# 5V_Power_Supply.net
KiCad netlist of a schematic drawn in Altium Designer
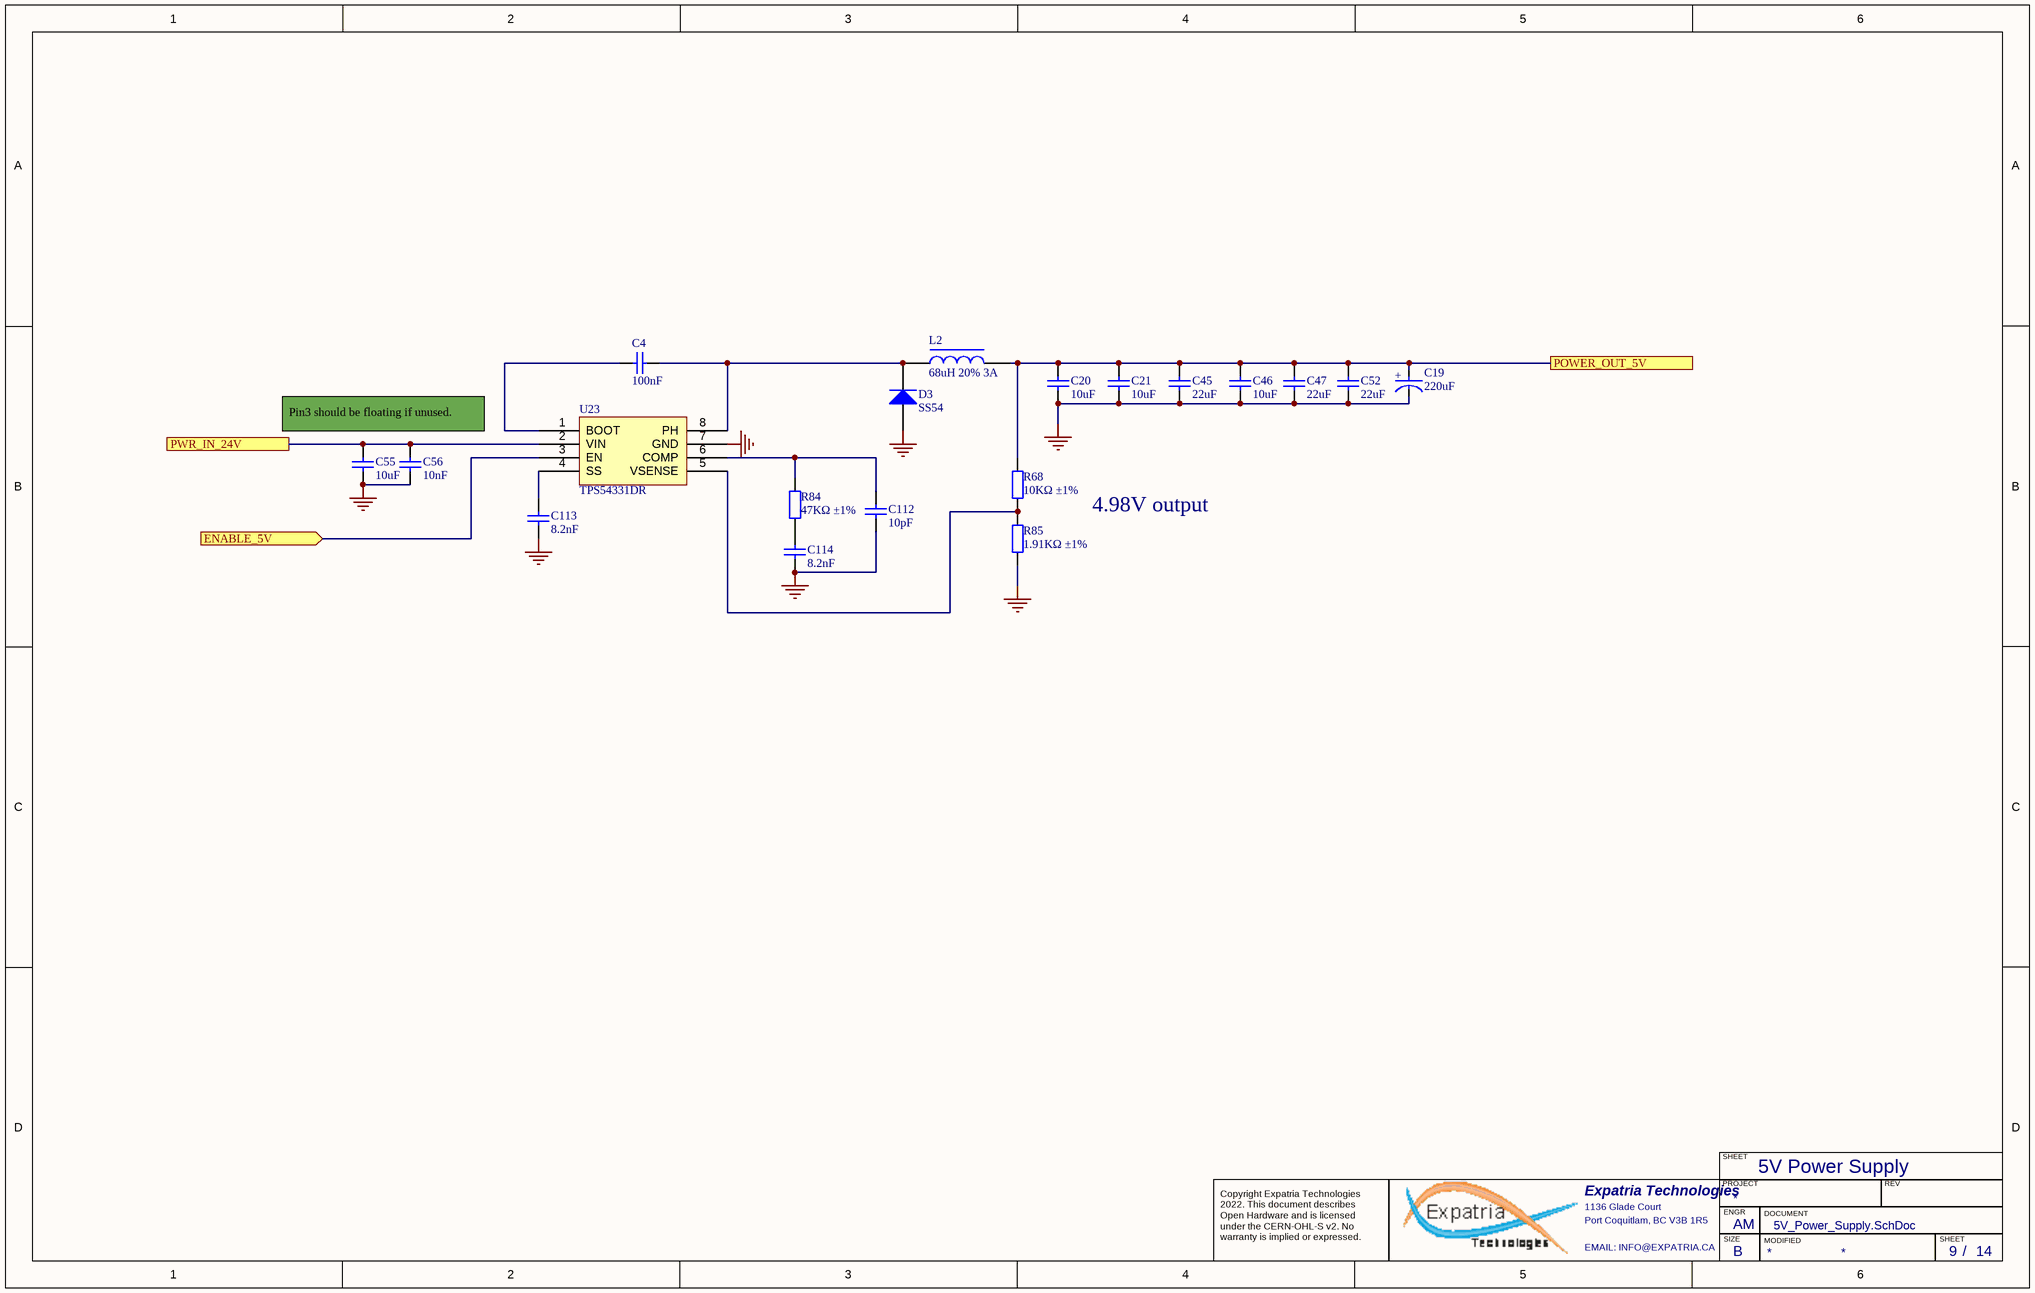
[diagram p0: 5V_Power_Supply.SchDoc]

(export (version "E")
  (design (tool "Eeschema 10.0.6"))
  (components
    (comp (ref "C4")
      (value "100nF")
      (footprint "0603_C")
      (description "50V 100nF X7R ±10% 0603 Multilayer Ceramic Capacitors MLCC - SMD/SMT ROHS")
      (fields
        (field (name "MANUFACTURER") "YAGEO")
        (field (name "MANUFACTURER PART NUMBER") "CC0603KRX7R9BB104")
      )
      (libsource (lib "Sienci_Labs") (part "0603 100nF (104) 10% 50V"))
    )
    (comp (ref "C19")
      (value "UUD1H221MNL1GS")
      (footprint "FP-FKG-MFG")
      (description "CAP ALUM 220UF 20% 50V SMD")
      (fields
        (field (name "TOLERANCE") "20%")
        (field (name "CAPACITANCE") "220uF")
        (field (name "MANUFACTURER") "Nichicon")
        (field (name "SOURCE") "Sienci_Labs.SchLib")
      )
      (libsource (lib "Cambridge Mobile Telematics, Inc") (part "UUD1H221MNL1GS"))
    )
    (comp (ref "C20")
      (value "10uF")
      (footprint "1206_C")
      (description "50V 10uF X5R ±10% 1206 Multilayer Ceramic Capacitors MLCC - SMD/SMT ROHS")
      (fields
        (field (name "MANUFACTURER") "Samsung Electro-Mechanics")
        (field (name "MANUFACTURER PART NUMBER") "CL31A106KBHNNNE")
      )
      (libsource (lib "Sienci_Labs") (part "1206 10uF (106) 10% 50V"))
    )
    (comp (ref "C21")
      (value "10uF")
      (footprint "1206_C")
      (description "50V 10uF X5R ±10% 1206 Multilayer Ceramic Capacitors MLCC - SMD/SMT ROHS")
      (fields
        (field (name "MANUFACTURER") "Samsung Electro-Mechanics")
        (field (name "MANUFACTURER PART NUMBER") "CL31A106KBHNNNE")
      )
      (libsource (lib "Sienci_Labs") (part "1206 10uF (106) 10% 50V"))
    )
    (comp (ref "C45")
      (value "22uF")
      (footprint "0805_C")
      (description "25V 22uF X5R ±20% 0805 Multilayer Ceramic Capacitors MLCC - SMD/SMT ROHS")
      (fields (field (name "MANUFACTURER") "Samsung Electro-Mechanics") (field (name "TOLERANCE") "20%"))
      (libsource (lib "Sienci_Labs") (part "0805 22uF (226) 20% 25V"))
    )
    (comp (ref "C46")
      (value "10uF")
      (footprint "1206_C")
      (description "50V 10uF X5R ±10% 1206 Multilayer Ceramic Capacitors MLCC - SMD/SMT ROHS")
      (fields
        (field (name "MANUFACTURER") "Samsung Electro-Mechanics")
        (field (name "MANUFACTURER PART NUMBER") "CL31A106KBHNNNE")
      )
      (libsource (lib "Sienci_Labs") (part "1206 10uF (106) 10% 50V"))
    )
    (comp (ref "C47")
      (value "22uF")
      (footprint "0805_C")
      (description "25V 22uF X5R ±20% 0805 Multilayer Ceramic Capacitors MLCC - SMD/SMT ROHS")
      (fields (field (name "MANUFACTURER") "Samsung Electro-Mechanics") (field (name "TOLERANCE") "20%"))
      (libsource (lib "Sienci_Labs") (part "0805 22uF (226) 20% 25V"))
    )
    (comp (ref "C52")
      (value "22uF")
      (footprint "0805_C")
      (description "25V 22uF X5R ±20% 0805 Multilayer Ceramic Capacitors MLCC - SMD/SMT ROHS")
      (fields (field (name "MANUFACTURER") "Samsung Electro-Mechanics") (field (name "TOLERANCE") "20%"))
      (libsource (lib "Sienci_Labs") (part "0805 22uF (226) 20% 25V"))
    )
    (comp (ref "C55")
      (value "10uF")
      (footprint "1206_C")
      (description "50V 10uF X5R ±10% 1206 Multilayer Ceramic Capacitors MLCC - SMD/SMT ROHS")
      (fields
        (field (name "MANUFACTURER") "Samsung Electro-Mechanics")
        (field (name "MANUFACTURER PART NUMBER") "CL31A106KBHNNNE")
      )
      (libsource (lib "Sienci_Labs") (part "1206 10uF (106) 10% 50V"))
    )
    (comp (ref "C56")
      (value "10nF")
      (footprint "0603_C")
      (description "50V 10nF X7R ±10% 0603 Multilayer Ceramic Capacitors MLCC - SMD/SMT ROHS")
      (fields
        (field (name "MANUFACTURER") "Guangdong Fenghua Advanced Tech")
        (field (name "TOLERANCE") "10%")
      )
      (libsource (lib "Sienci_Labs") (part "0603 10nF (103) 10% 50V"))
    )
    (comp (ref "C112")
      (value "10pF")
      (footprint "0603_C")
      (description "Chip capacitors")
      (fields
        (field (name "MANUFACTURER") "Samsung Electro-Mechanics")
        (field (name "MANUFACTURER PART NUMBER") "CL10C100JB8NNNC")
      )
      (libsource (lib "Cap") (part "0603 10pF (100) 5% 50V"))
    )
    (comp (ref "C113")
      (value "8.2nF")
      (footprint "0603_C")
      (description "50V 8.2nF X7R ±10% 0603 Multilayer Ceramic Capacitors MLCC - SMD/SMT ROHS")
      (fields (field (name "MANUFACTURER") "YAGEO") (field (name "TOLERANCE") "10%"))
      (libsource (lib "Sienci_Labs") (part "0603 8.2nF (822) 10% 50V"))
    )
    (comp (ref "C114")
      (value "8.2nF")
      (footprint "0603_C")
      (description "50V 8.2nF X7R ±10% 0603 Multilayer Ceramic Capacitors MLCC - SMD/SMT ROHS")
      (fields (field (name "MANUFACTURER") "YAGEO") (field (name "TOLERANCE") "10%"))
      (libsource (lib "Sienci_Labs") (part "0603 8.2nF (822) 10% 50V"))
    )
    (comp (ref "D3")
      (value "SS54")
      (footprint "SMA(DO-214AC)_S1")
      (description "40V 5A 550mV@5A")
      (fields (field (name "MANUFACTURER") "MDD"))
      (libsource (lib "Diode") (part "SMA(DO-214AC) SS54"))
    )
    (comp (ref "L2")
      (value "68uH 20% 3A")
      (footprint "INDP126126X68N")
      (description "3A 68uH ±20% 64.8mΩ SMD Inductors (SMD) ROHS")
      (libsource (lib "Cambridge Mobile Telematics, Inc") (part "12.5x12.5x6.5 68uH 20% 3A"))
    )
    (comp (ref "R68")
      (value "10KΩ ±1%")
      (footprint "0603_R")
      (description "Chip resistor")
      (fields
        (field (name "MANUFACTURER") "Uniroyal Elec")
        (field (name "MANUFACTURER PART NUMBER") "0603WAF1002T5E")
      )
      (libsource (lib "Sienci_Labs") (part "0603 10K (1002) 1%"))
    )
    (comp (ref "R84")
      (value "47KΩ ±1%")
      (footprint "0603_R")
      (description "Chip resistor")
      (fields
        (field (name "MANUFACTURER") "Uniroyal Elec")
        (field (name "MANUFACTURER PART NUMBER") "0603WAF4702T5E")
      )
      (libsource (lib "RES") (part "0603 47K (4702) 1%"))
    )
    (comp (ref "R85")
      (value "1.91KΩ ±1%")
      (footprint "0603_R")
      (description "Chip resistor")
      (fields (field (name "MANUFACTURER") "TyoHM") (field (name "POWER") "1/10W"))
      (libsource (lib "RES") (part "0603 1.91K (2001) 1%"))
    )
    (comp (ref "U23")
      (value "TPS54331DR")
      (footprint "Miscellaneous Devices LC:SOIC-8_150mil")
      (description "Switching Voltage Regulators 3A 28V In Step Down SWIFT DC/DC Cnvrtr")
      (fields (field (name "MANUFACTURER") "Texas Instruments"))
      (libsource (lib "PrintNC_GRBLHAL_Breakout") (part "TPS54331DR_[C9865]"))
    )
  )
  (nets
    (net (code "1") (name "/ENABLE_5V") (class "Default")
      (node (ref "U23") (pin "3") (pinfunction "EN_3") (pintype "passive"))
    )
    (net (code "2") (name "/POWER_OUT_5V") (class "Default")
      (node (ref "C19") (pin "2") (pinfunction "A_2") (pintype "passive"))
      (node (ref "C20") (pin "2") (pinfunction "2_2") (pintype "passive"))
      (node (ref "C21") (pin "2") (pinfunction "2_2") (pintype "passive"))
      (node (ref "C45") (pin "2") (pinfunction "2_2") (pintype "passive"))
      (node (ref "C46") (pin "2") (pinfunction "2_2") (pintype "passive"))
      (node (ref "C47") (pin "2") (pinfunction "2_2") (pintype "passive"))
      (node (ref "C52") (pin "2") (pinfunction "2_2") (pintype "passive"))
      (node (ref "L2") (pin "2") (pinfunction "2_2") (pintype "passive"))
      (node (ref "R68") (pin "2") (pinfunction "2_2") (pintype "passive"))
    )
    (net (code "3") (name "/PWR_IN_24V") (class "Default")
      (node (ref "C55") (pin "2") (pinfunction "2_2") (pintype "passive"))
      (node (ref "C56") (pin "2") (pinfunction "2_2") (pintype "passive"))
      (node (ref "U23") (pin "2") (pinfunction "VIN_2") (pintype "passive"))
    )
    (net (code "4") (name "GND") (class "Default")
      (node (ref "C112") (pin "1") (pinfunction "1_1") (pintype "passive"))
      (node (ref "C113") (pin "1") (pinfunction "1_1") (pintype "passive"))
      (node (ref "C114") (pin "1") (pinfunction "1_1") (pintype "passive"))
      (node (ref "C19") (pin "1") (pinfunction "C_1") (pintype "passive"))
      (node (ref "C20") (pin "1") (pinfunction "1_1") (pintype "passive"))
      (node (ref "C21") (pin "1") (pinfunction "1_1") (pintype "passive"))
      (node (ref "C45") (pin "1") (pinfunction "1_1") (pintype "passive"))
      (node (ref "C46") (pin "1") (pinfunction "1_1") (pintype "passive"))
      (node (ref "C47") (pin "1") (pinfunction "1_1") (pintype "passive"))
      (node (ref "C52") (pin "1") (pinfunction "1_1") (pintype "passive"))
      (node (ref "C55") (pin "1") (pinfunction "1_1") (pintype "passive"))
      (node (ref "C56") (pin "1") (pinfunction "1_1") (pintype "passive"))
      (node (ref "D3") (pin "1") (pinfunction "A_1") (pintype "passive"))
      (node (ref "R85") (pin "1") (pinfunction "1_1") (pintype "passive"))
      (node (ref "U23") (pin "7") (pinfunction "GND_7") (pintype "passive"))
    )
    (net (code "5") (name "Net-(C114-Pad2)") (class "Default")
      (node (ref "C114") (pin "2") (pinfunction "2_2") (pintype "passive"))
      (node (ref "R84") (pin "1") (pinfunction "1_1") (pintype "passive"))
    )
    (net (code "6") (name "Net-(D3-K)") (class "Default")
      (node (ref "C4") (pin "2") (pinfunction "2_2") (pintype "passive"))
      (node (ref "D3") (pin "2") (pinfunction "K_2") (pintype "passive"))
      (node (ref "L2") (pin "1") (pinfunction "1_1") (pintype "passive"))
      (node (ref "U23") (pin "8") (pinfunction "PH_8") (pintype "passive"))
    )
    (net (code "7") (name "Net-(U23-BOOT)") (class "Default")
      (node (ref "C4") (pin "1") (pinfunction "1_1") (pintype "passive"))
      (node (ref "U23") (pin "1") (pinfunction "BOOT_1") (pintype "passive"))
    )
    (net (code "8") (name "Net-(U23-COMP)") (class "Default")
      (node (ref "C112") (pin "2") (pinfunction "2_2") (pintype "passive"))
      (node (ref "R84") (pin "2") (pinfunction "2_2") (pintype "passive"))
      (node (ref "U23") (pin "6") (pinfunction "COMP_6") (pintype "passive"))
    )
    (net (code "9") (name "Net-(U23-SS)") (class "Default")
      (node (ref "C113") (pin "2") (pinfunction "2_2") (pintype "passive"))
      (node (ref "U23") (pin "4") (pinfunction "SS_4") (pintype "passive"))
    )
    (net (code "10") (name "Net-(U23-VSENSE)") (class "Default")
      (node (ref "R68") (pin "1") (pinfunction "1_1") (pintype "passive"))
      (node (ref "R85") (pin "2") (pinfunction "2_2") (pintype "passive"))
      (node (ref "U23") (pin "5") (pinfunction "VSENSE_5") (pintype "passive"))
    )
  )
)
